# featherFet.net
KiCad netlist of a schematic drawn in Altium Designer
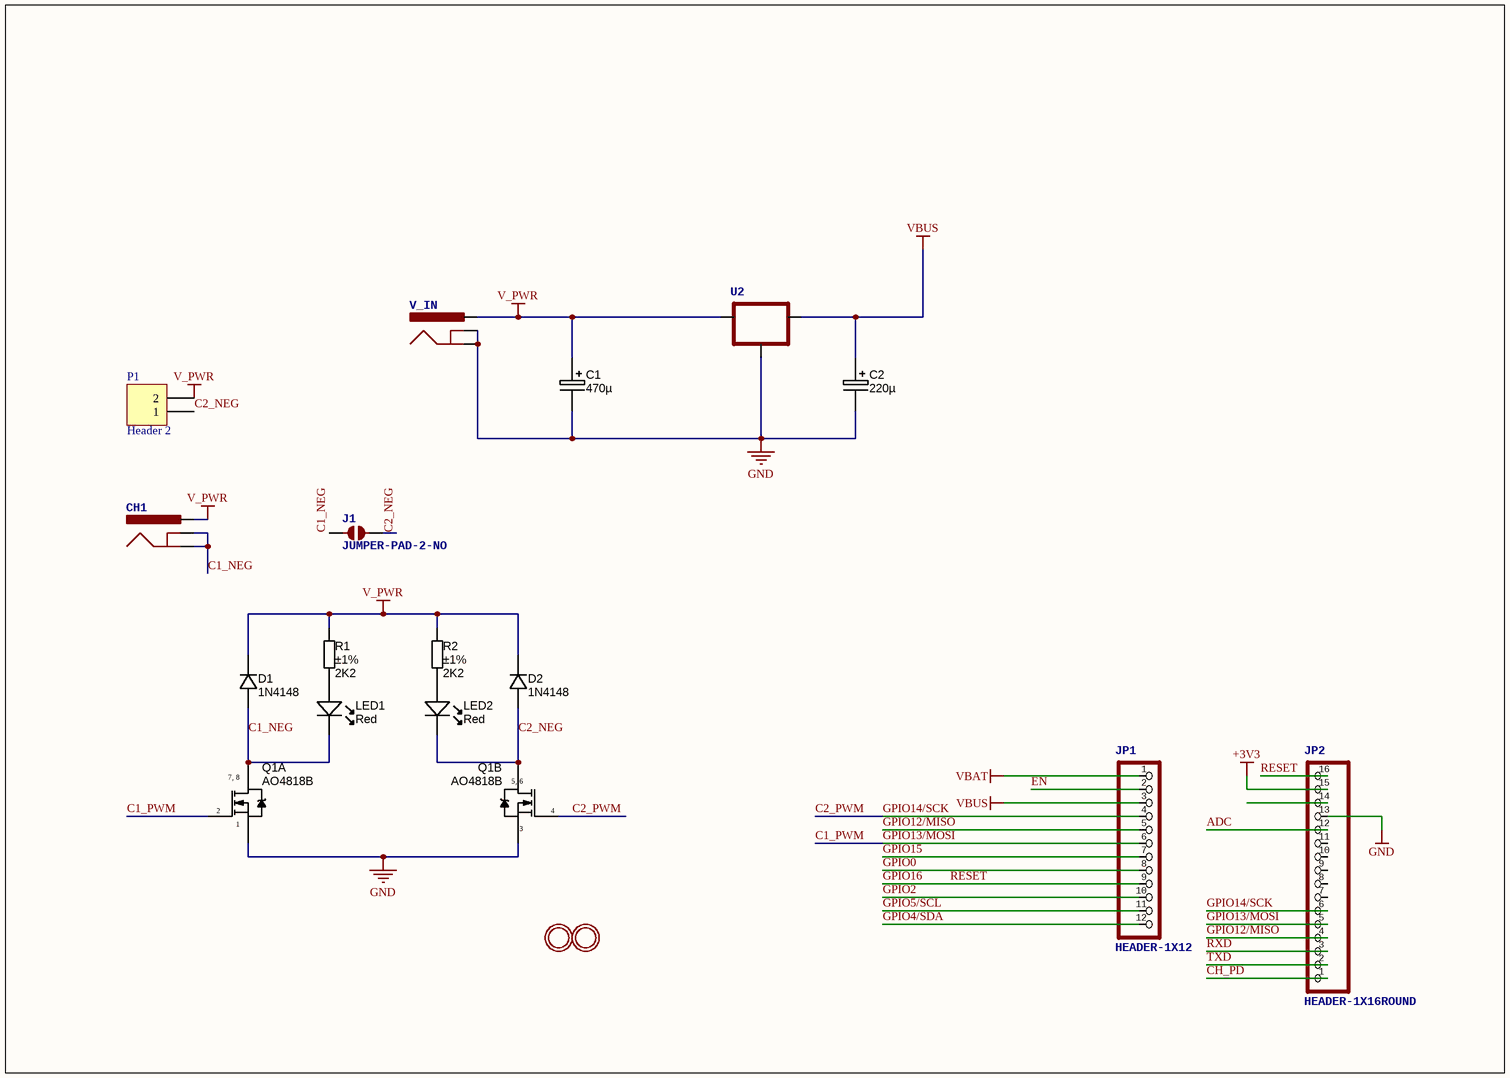
[diagram p0: featherFet.SchDoc]

(export (version "E")
  (design (tool "Eeschema 10.0.6"))
  (components
    (comp (ref "C1")
      (value "470µ")
      (footprint "CAPE10.0MM_Rad_10x14mm")
      (description "Capacitor THT Alum Elec 470uF 20% 16V")
      (fields (field (name "TOLERANCE") "±20%"))
      (libsource (lib "PBL - Capacitors") (part "CAPE_470u_16V_THT"))
    )
    (comp (ref "C2")
      (value "220µ")
      (footprint "CAPE3.5mm")
      (description "Capacitor THT Alum Elec 220uF 20% 16V")
      (fields (field (name "TOLERANCE") "±20%"))
      (libsource (lib "PBL - Capacitors") (part "CAPE_220u_16V_THD"))
    )
    (comp (ref "CH1")
      (value "Power JackThis is the standard 5.5mm barrel jack for power. The PTH is the most common, proven, reliable, footprint. The Slot footprint only works if the mill layer is transmitted to the PCB fab house so be warned. Mating wall wart : TOL-00298 (and others)")
      (footprint "POWER_JACK_PTH")
      (libsource (lib "SparkFun-Connectors") (part "POWER_JACKPTH"))
    )
    (comp (ref "D1")
      (value "1N4148")
      (footprint "SOD523F")
      (description "Diode SMD small signal 0.2A SOD-523F")
      (libsource (lib "PBL - Diodes") (part "DIODE_1N4148_200mA_SOD523F"))
    )
    (comp (ref "D2")
      (value "1N4148")
      (footprint "SOD523F")
      (description "Diode SMD small signal 0.2A SOD-523F")
      (libsource (lib "PBL - Diodes") (part "DIODE_1N4148_200mA_SOD523F"))
    )
    (comp (ref "J1")
      (value "JUMPER-PAD-2-NO")
      (footprint "PAD-JUMPER-2-NO_NO_SILK")
      (libsource (lib "SparkFun-Passives") (part "JUMPER-PAD-2-NO"))
    )
    (comp (ref "JP1")
      (value "HEADER-1X12")
      (footprint "1X12_ROUND")
      (fields (field (name "DRAWN") "KTOWN"))
      (libsource (lib "microbuilder") (part "HEADER-1X12"))
    )
    (comp (ref "JP2")
      (value "HEADER-1X16ROUND")
      (footprint "1X16_ROUND")
      (description "PIN HEADER")
      (fields (field (name "DRAWN") "KTOWN"))
      (libsource (lib "microbuilder") (part "HEADER-1X16ROUND"))
    )
    (comp (ref "LED1")
      (value "~")
      (footprint "LED-0805-K")
      (description "LED 0805 SMD Red 6mcd 621nm")
      (fields (field (name "COLOR") "Red"))
      (libsource (lib "PBL - Light Sources") (part "LED_SMD_Red_0805_6mcd"))
    )
    (comp (ref "LED2")
      (value "~")
      (footprint "LED-0805-K")
      (description "LED 0805 SMD Red 6mcd 621nm")
      (fields (field (name "COLOR") "Red"))
      (libsource (lib "PBL - Light Sources") (part "LED_SMD_Red_0805_6mcd"))
    )
    (comp (ref "P1")
      (value "Header 2")
      (footprint "HDR1X2")
      (description "Header, 2-Pin")
      (fields (field (name "PUBLISHER") "Altium Limited"))
      (libsource (lib "Miscellaneous Connectors") (part "Header 2"))
    )
    (comp (ref "Q1")
      (value "MOSFET_AO4818B")
      (footprint "SOIC127P600X175-8AN")
      (description "MOSFET Dual-Channel 30V 8.5A SOIC-8 SMD")
      (fields (field (name "MANUFACTURER PART NUMBER 1") "AO4818B"))
      (libsource (lib "PBL - Transistors") (part "MOSFET_AO4818B"))
    )
    (comp (ref "R1")
      (value "2K2")
      (footprint "RESC2012X70N")
      (description "Resistor SMD chip 2.2k Ohm 0.125W 1% 0805")
      (fields (field (name "TOLERANCE") "±1%") (field (name "Comment") "Thick Film"))
      (libsource (lib "PBL - Resistors") (part "RES_2K2_0805_1%"))
    )
    (comp (ref "R2")
      (value "2K2")
      (footprint "RESC2012X70N")
      (description "Resistor SMD chip 2.2k Ohm 0.125W 1% 0805")
      (fields (field (name "TOLERANCE") "±1%") (field (name "Comment") "Thick Film"))
      (libsource (lib "PBL - Resistors") (part "RES_2K2_0805_1%"))
    )
    (comp (ref "U$31")
      (value "MOUNTINGHOLE2.5")
      (footprint "MOUNTINGHOLE_2.5_PLATED")
      (description "Mounting Hole   For #2 screws (0.086\"/2.18mm width, 0.094\"/2.4mm hole) use 2.5mm")
      (fields (field (name "DRAWN") "KTOWN"))
      (libsource (lib "microbuilder") (part "MOUNTINGHOLE2.5"))
    )
    (comp (ref "U$32")
      (value "MOUNTINGHOLE2.5")
      (footprint "MOUNTINGHOLE_2.5_PLATED")
      (description "Mounting Hole   For #2 screws (0.086\"/2.18mm width, 0.094\"/2.4mm hole) use 2.5mm")
      (fields (field (name "DRAWN") "KTOWN"))
      (libsource (lib "microbuilder") (part "MOUNTINGHOLE2.5"))
    )
    (comp (ref "U2")
      (value "Voltage RegulatorStandard 78xx regulator. IGO (Input Ground Output). Spark Fun Electronics SKU : COM-00107")
      (footprint "TO220-IGO")
      (libsource (lib "SparkFun-PowerIC") (part "V_REG_78XXSINK"))
    )
    (comp (ref "V_IN")
      (value "Power JackThis is the standard 5.5mm barrel jack for power. The PTH is the most common, proven, reliable, footprint. The Slot footprint only works if the mill layer is transmitted to the PCB fab house so be warned. Mating wall wart : TOL-00298 (and others)")
      (footprint "POWER_JACK_PTH")
      (libsource (lib "SparkFun-Connectors") (part "POWER_JACKPTH"))
    )
  )
  (nets
    (net (code "1") (name "+3V3") (class "Default")
      (node (ref "JP2") (pin "15") (pinfunction "15_15") (pintype "passive"))
    )
    (net (code "2") (name "/ADC") (class "Default")
      (node (ref "JP2") (pin "12") (pinfunction "12_12") (pintype "passive"))
    )
    (net (code "3") (name "/C1_NEG") (class "Default")
      (node (ref "CH1") (pin "GND") (pinfunction "GND_GND") (pintype "passive"))
      (node (ref "CH1") (pin "GNDBREAK") (pinfunction "GNDBREAK_GNDBREAK") (pintype "passive"))
      (node (ref "D1") (pin "A") (pinfunction "A_A") (pintype "passive"))
      (node (ref "J1") (pin "1") (pinfunction "1_1") (pintype "passive"))
      (node (ref "LED1") (pin "K") (pinfunction "K_K") (pintype "passive"))
      (node (ref "Q1") (pin "7") (pinfunction "D_7") (pintype "passive"))
      (node (ref "Q1") (pin "8") (pinfunction "D_8") (pintype "passive"))
    )
    (net (code "4") (name "/C1_PWM") (class "Default")
      (node (ref "JP1") (pin "6") (pinfunction "6_6") (pintype "passive"))
      (node (ref "JP2") (pin "5") (pinfunction "5_5") (pintype "passive"))
      (node (ref "Q1") (pin "2") (pinfunction "G_2") (pintype "passive"))
    )
    (net (code "5") (name "/C2_NEG") (class "Default")
      (node (ref "D2") (pin "A") (pinfunction "A_A") (pintype "passive"))
      (node (ref "J1") (pin "2") (pinfunction "2_2") (pintype "passive"))
      (node (ref "LED2") (pin "K") (pinfunction "K_K") (pintype "passive"))
      (node (ref "P1") (pin "1") (pinfunction "1_1") (pintype "passive"))
      (node (ref "Q1") (pin "5") (pinfunction "D_5") (pintype "passive"))
      (node (ref "Q1") (pin "6") (pinfunction "D_6") (pintype "passive"))
    )
    (net (code "6") (name "/C2_PWM") (class "Default")
      (node (ref "JP1") (pin "4") (pinfunction "4_4") (pintype "passive"))
      (node (ref "JP2") (pin "6") (pinfunction "6_6") (pintype "passive"))
      (node (ref "Q1") (pin "4") (pinfunction "G_4") (pintype "passive"))
    )
    (net (code "7") (name "/CH_PD") (class "Default")
      (node (ref "JP2") (pin "1") (pinfunction "1_1") (pintype "passive"))
    )
    (net (code "8") (name "/EN") (class "Default")
      (node (ref "JP1") (pin "2") (pinfunction "2_2") (pintype "passive"))
    )
    (net (code "9") (name "/GPIO0") (class "Default")
      (node (ref "JP1") (pin "8") (pinfunction "8_8") (pintype "passive"))
    )
    (net (code "10") (name "/GPIO2") (class "Default")
      (node (ref "JP1") (pin "10") (pinfunction "10_10") (pintype "passive"))
    )
    (net (code "11") (name "/GPIO4{slash}SDA") (class "Default")
      (node (ref "JP1") (pin "12") (pinfunction "12_12") (pintype "passive"))
    )
    (net (code "12") (name "/GPIO5{slash}SCL") (class "Default")
      (node (ref "JP1") (pin "11") (pinfunction "11_11") (pintype "passive"))
    )
    (net (code "13") (name "/GPIO12{slash}MISO") (class "Default")
      (node (ref "JP1") (pin "5") (pinfunction "5_5") (pintype "passive"))
      (node (ref "JP2") (pin "4") (pinfunction "4_4") (pintype "passive"))
    )
    (net (code "14") (name "/GPIO15") (class "Default")
      (node (ref "JP1") (pin "7") (pinfunction "7_7") (pintype "passive"))
    )
    (net (code "15") (name "/GPIO16") (class "Default")
      (node (ref "JP1") (pin "9") (pinfunction "9_9") (pintype "passive"))
      (node (ref "JP2") (pin "16") (pinfunction "16_16") (pintype "passive"))
    )
    (net (code "16") (name "/RXD") (class "Default")
      (node (ref "JP2") (pin "3") (pinfunction "3_3") (pintype "passive"))
    )
    (net (code "17") (name "/TXD") (class "Default")
      (node (ref "JP2") (pin "2") (pinfunction "2_2") (pintype "passive"))
    )
    (net (code "18") (name "GND") (class "Default")
      (node (ref "C1") (pin "2") (pintype "passive"))
      (node (ref "C2") (pin "2") (pintype "passive"))
      (node (ref "JP2") (pin "13") (pinfunction "13_13") (pintype "passive"))
      (node (ref "Q1") (pin "1") (pinfunction "S_1") (pintype "passive"))
      (node (ref "Q1") (pin "3") (pinfunction "S_3") (pintype "passive"))
      (node (ref "U2") (pin "GND") (pinfunction "GND_GND") (pintype "passive"))
      (node (ref "V_IN") (pin "GND") (pinfunction "GND_GND") (pintype "passive"))
      (node (ref "V_IN") (pin "GNDBREAK") (pinfunction "GNDBREAK_GNDBREAK") (pintype "passive"))
    )
    (net (code "19") (name "Net-(LED1-PadA)") (class "Default")
      (node (ref "LED1") (pin "A") (pinfunction "A_A") (pintype "passive"))
      (node (ref "R1") (pin "2") (pinfunction "2_2") (pintype "passive"))
    )
    (net (code "20") (name "Net-(LED2-PadA)") (class "Default")
      (node (ref "LED2") (pin "A") (pinfunction "A_A") (pintype "passive"))
      (node (ref "R2") (pin "2") (pinfunction "2_2") (pintype "passive"))
    )
    (net (code "21") (name "VBAT") (class "Default")
      (node (ref "JP1") (pin "1") (pinfunction "1_1") (pintype "passive"))
    )
    (net (code "22") (name "VBUS") (class "Default")
      (node (ref "C2") (pin "1") (pintype "passive"))
      (node (ref "JP1") (pin "3") (pinfunction "3_3") (pintype "passive"))
      (node (ref "U2") (pin "OUT") (pinfunction "OUT_OUT") (pintype "passive"))
    )
    (net (code "23") (name "V_PWR") (class "Default")
      (node (ref "C1") (pin "1") (pintype "passive"))
      (node (ref "CH1") (pin "PWR") (pinfunction "PWR_PWR") (pintype "passive"))
      (node (ref "D1") (pin "K") (pinfunction "K_K") (pintype "passive"))
      (node (ref "D2") (pin "K") (pinfunction "K_K") (pintype "passive"))
      (node (ref "P1") (pin "2") (pinfunction "2_2") (pintype "passive"))
      (node (ref "R1") (pin "1") (pinfunction "1_1") (pintype "passive"))
      (node (ref "R2") (pin "1") (pinfunction "1_1") (pintype "passive"))
      (node (ref "U2") (pin "IN") (pinfunction "IN_IN") (pintype "passive"))
      (node (ref "V_IN") (pin "PWR") (pinfunction "PWR_PWR") (pintype "passive"))
    )
    (net (code "24") (name "unconnected-(JP2-Pad7)") (class "Default")
      (node (ref "JP2") (pin "7") (pinfunction "7_7") (pintype "passive"))
    )
    (net (code "25") (name "unconnected-(JP2-Pad8)") (class "Default")
      (node (ref "JP2") (pin "8") (pinfunction "8_8") (pintype "passive"))
    )
    (net (code "26") (name "unconnected-(JP2-Pad9)") (class "Default")
      (node (ref "JP2") (pin "9") (pinfunction "9_9") (pintype "passive"))
    )
    (net (code "27") (name "unconnected-(JP2-Pad10)") (class "Default")
      (node (ref "JP2") (pin "10") (pinfunction "10_10") (pintype "passive"))
    )
    (net (code "28") (name "unconnected-(JP2-Pad11)") (class "Default")
      (node (ref "JP2") (pin "11") (pinfunction "11_11") (pintype "passive"))
    )
    (net (code "29") (name "unconnected-(JP2-Pad14)") (class "Default")
      (node (ref "JP2") (pin "14") (pinfunction "14_14") (pintype "passive"))
    )
  )
)
